# TSOC_USBUART2_pwr.net
KiCad netlist of a schematic drawn in EAGLE
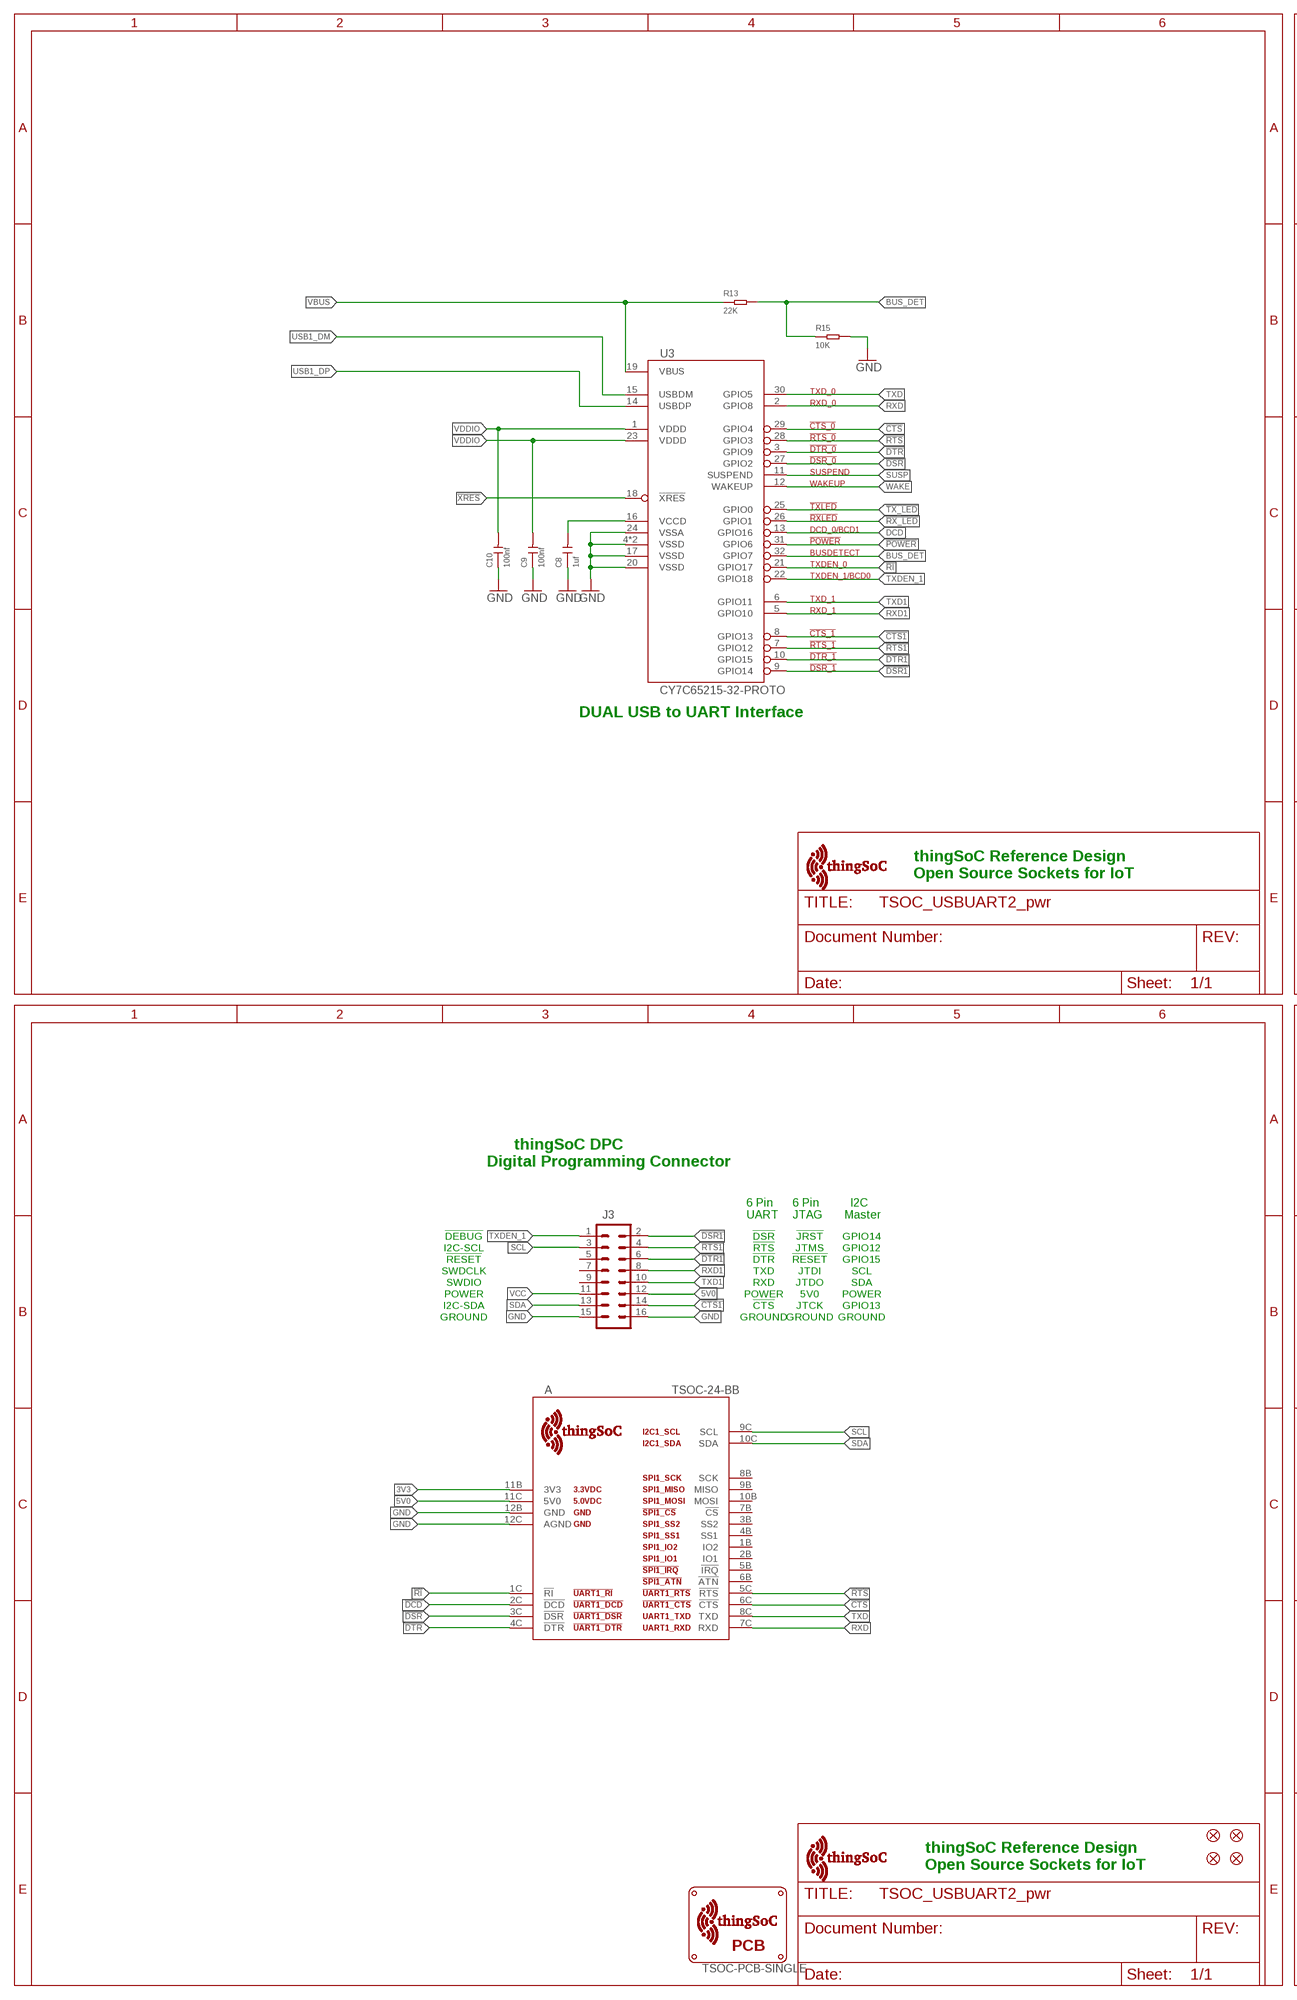
[diagram p0: schematic, sheet 1, part 1 of 2]
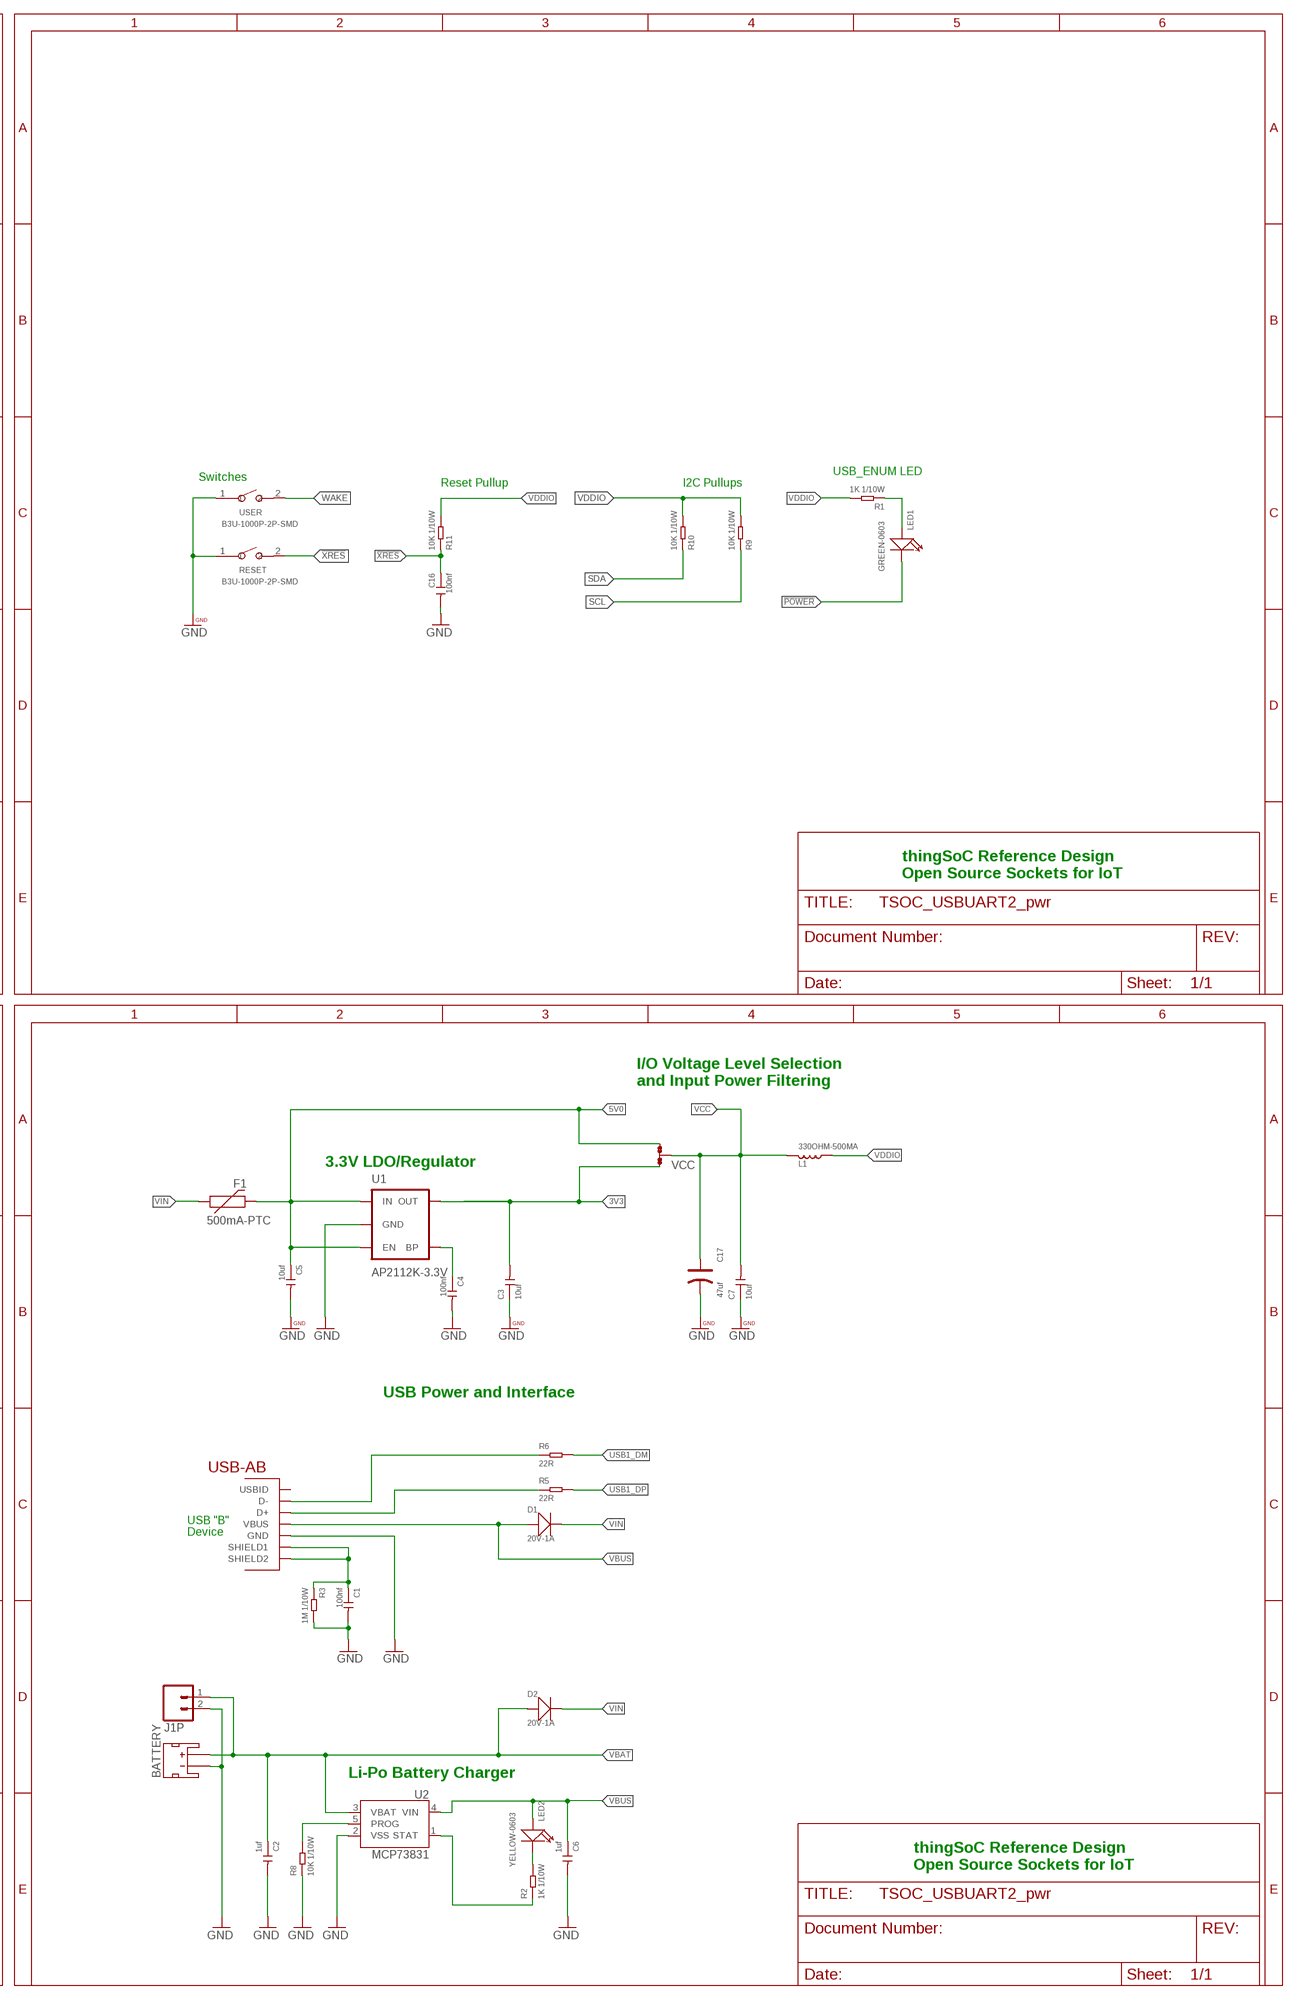
[diagram p1: schematic, sheet 1, part 2 of 2]

(export (version "E")
  (design (tool "Eeschema 10.0.6"))
  (components
    (comp (ref "A")
      (value "TSOC-24-BB")
      (footprint "eagle-import:TSOC-BB-S24")
      (libsource (lib "eagle-import") (part "TSOC-24-BB"))
    )
    (comp (ref "BATTERY")
      (value "JST_2MM_MALE")
      (footprint "eagle-import:JST-2-SMD")
      (libsource (lib "eagle-import") (part "JST_2MM_MALE"))
    )
    (comp (ref "C1")
      (value "100nf")
      (footprint "eagle-import:C0603")
      (fields (field (name "MPN") "CC0603KRX7R9BB104"))
      (libsource (lib "eagle-import") (part "CERAMIC-100NF-50V-10%-X7R(0603)"))
    )
    (comp (ref "C2")
      (value "1uf")
      (footprint "eagle-import:C0603")
      (fields (field (name "MPN") "CC0603KRX7R8BB105"))
      (libsource (lib "eagle-import") (part "CERAMIC-1UF-25V-10%-X7R(0603)"))
    )
    (comp (ref "C3")
      (value "10uf")
      (footprint "eagle-import:C0603")
      (fields (field (name "MPN") "CC0603KRX5R6BB106"))
      (libsource (lib "eagle-import") (part "CERAMIC-10UF-10V-10%-X5R(0603)"))
    )
    (comp (ref "C4")
      (value "100nf")
      (footprint "eagle-import:C0603")
      (fields (field (name "MPN") "CC0603KRX7R9BB104"))
      (libsource (lib "eagle-import") (part "CERAMIC-100NF-50V-10%-X7R(0603)"))
    )
    (comp (ref "C5")
      (value "10uf")
      (footprint "eagle-import:C0603")
      (fields (field (name "MPN") "CC0603KRX5R6BB106"))
      (libsource (lib "eagle-import") (part "CERAMIC-10UF-10V-10%-X5R(0603)"))
    )
    (comp (ref "C6")
      (value "1uf")
      (footprint "eagle-import:C0603")
      (fields (field (name "MPN") "CC0603KRX7R8BB105"))
      (libsource (lib "eagle-import") (part "CERAMIC-1UF-25V-10%-X7R(0603)"))
    )
    (comp (ref "C7")
      (value "10uf")
      (footprint "eagle-import:C0603")
      (fields (field (name "MPN") "CC0603KRX5R6BB106"))
      (libsource (lib "eagle-import") (part "CERAMIC-10UF-10V-10%-X5R(0603)"))
    )
    (comp (ref "C8")
      (value "1uf")
      (footprint "eagle-import:C0603")
      (fields (field (name "MPN") "CC0603KRX7R8BB105"))
      (libsource (lib "eagle-import") (part "CERAMIC-1UF-25V-10%-X7R(0603)"))
    )
    (comp (ref "C9")
      (value "100nf")
      (footprint "eagle-import:C0603")
      (fields (field (name "MPN") "CC0603KRX7R9BB104"))
      (libsource (lib "eagle-import") (part "CERAMIC-100NF-50V-10%-X7R(0603)"))
    )
    (comp (ref "C10")
      (value "100nf")
      (footprint "eagle-import:C0603")
      (fields (field (name "MPN") "CC0603KRX7R9BB104"))
      (libsource (lib "eagle-import") (part "CERAMIC-100NF-50V-10%-X7R(0603)"))
    )
    (comp (ref "C16")
      (value "100nf")
      (footprint "eagle-import:C0603")
      (fields (field (name "MPN") "CC0603KRX7R9BB104"))
      (libsource (lib "eagle-import") (part "CERAMIC-100NF-50V-10%-X7R(0603)"))
    )
    (comp (ref "C17")
      (value "47uf")
      (footprint "eagle-import:AVX-A")
      (fields (field (name "MPN") "TAJA476*006#NJ"))
      (libsource (lib "eagle-import") (part "TANTALUM-SMD-47UF-6.3V(AVX-A)"))
    )
    (comp (ref "D1")
      (value "20V-1A")
      (footprint "eagle-import:SOD-123")
      (fields (field (name "MPN") "B5819W"))
      (libsource (lib "eagle-import") (part "SMD-DIODE-SCHOTTKY-20V-1A(SOD-123)"))
    )
    (comp (ref "D2")
      (value "20V-1A")
      (footprint "eagle-import:SOD-123")
      (fields (field (name "MPN") "B5819W"))
      (libsource (lib "eagle-import") (part "SMD-DIODE-SCHOTTKY-20V-1A(SOD-123)"))
    )
    (comp (ref "F1")
      (value "500mA-PTC")
      (footprint "eagle-import:PTC-1206")
      (libsource (lib "eagle-import") (part "PTCSMD"))
    )
    (comp (ref "FID1")
      (value "FIDUCIALUFIDUCIAL")
      (footprint "eagle-import:MICRO-FIDUCIAL")
      (libsource (lib "eagle-import") (part "FIDUCIALUFIDUCIAL"))
    )
    (comp (ref "FID2")
      (value "FIDUCIALUFIDUCIAL")
      (footprint "eagle-import:MICRO-FIDUCIAL")
      (libsource (lib "eagle-import") (part "FIDUCIALUFIDUCIAL"))
    )
    (comp (ref "FID3")
      (value "FIDUCIALUFIDUCIAL")
      (footprint "eagle-import:MICRO-FIDUCIAL")
      (libsource (lib "eagle-import") (part "FIDUCIALUFIDUCIAL"))
    )
    (comp (ref "FID4")
      (value "FIDUCIALUFIDUCIAL")
      (footprint "eagle-import:MICRO-FIDUCIAL")
      (libsource (lib "eagle-import") (part "FIDUCIALUFIDUCIAL"))
    )
    (comp (ref "J1P")
      (value "M02-JST-2-PTH-NO_SILK")
      (footprint "eagle-import:JST-2-PTH-NS")
      (libsource (lib "eagle-import") (part "M02-JST-2-PTH-NO_SILK"))
    )
    (comp (ref "J3")
      (value "M08X2")
      (footprint "eagle-import:2X8")
      (libsource (lib "eagle-import") (part "M08X2"))
    )
    (comp (ref "L1")
      (value "330OHM-500MA")
      (footprint "eagle-import:L0603")
      (fields (field (name "MPN") "BLM18AG121SN1D"))
      (libsource (lib "eagle-import") (part "SMD-FERRITE-CHIP-120-OHM-500MA(0603)"))
    )
    (comp (ref "LED1")
      (value "GREEN-0603")
      (footprint "eagle-import:LED-0603")
      (fields (field (name "MPN") "19-217-G7C-AN1P2-3T"))
      (libsource (lib "eagle-import") (part "SMD-LED-CLEAR-GREEN(0603)"))
    )
    (comp (ref "LED2")
      (value "YELLOW-0603")
      (footprint "eagle-import:LED-0603")
      (fields (field (name "MPN") "19-217-Y5C-AM1N1VY-3T"))
      (libsource (lib "eagle-import") (part "SMD-LED-CLEAR-YELLOW(0603)"))
    )
    (comp (ref "R1")
      (value "1K 1/10W")
      (footprint "eagle-import:R0603")
      (fields (field (name "MPN") "RC0603JR-071KL"))
      (libsource (lib "eagle-import") (part "SMD-RES-1K-5%-1/10W(0603)"))
    )
    (comp (ref "R2")
      (value "1K 1/10W")
      (footprint "eagle-import:R0603")
      (fields (field (name "MPN") "RC0603JR-071KL"))
      (libsource (lib "eagle-import") (part "SMD-RES-1K-5%-1/10W(0603)"))
    )
    (comp (ref "R3")
      (value "1M 1/10W")
      (footprint "eagle-import:R0603")
      (fields (field (name "MPN") "RC0603JR-071ML"))
      (libsource (lib "eagle-import") (part "SMD-RES-1M-5%-1/10W(0603)"))
    )
    (comp (ref "R5")
      (value "22R")
      (footprint "eagle-import:R0603")
      (fields (field (name "MPN") "RC0603JR-0722RL"))
      (libsource (lib "eagle-import") (part "SMD-RES-22R-5%-1/10W(0603)"))
    )
    (comp (ref "R6")
      (value "22R")
      (footprint "eagle-import:R0603")
      (fields (field (name "MPN") "RC0603JR-0722RL"))
      (libsource (lib "eagle-import") (part "SMD-RES-22R-5%-1/10W(0603)"))
    )
    (comp (ref "R8")
      (value "10K 1/10W")
      (footprint "eagle-import:R0603")
      (fields (field (name "MPN") "RC0603JR-0710KL"))
      (libsource (lib "eagle-import") (part "SMD-RES-10K-5%-1/10W(0603)"))
    )
    (comp (ref "R9")
      (value "10K 1/10W")
      (footprint "eagle-import:R0603")
      (fields (field (name "MPN") "RC0603JR-0710KL"))
      (libsource (lib "eagle-import") (part "SMD-RES-10K-5%-1/10W(0603)"))
    )
    (comp (ref "R10")
      (value "10K 1/10W")
      (footprint "eagle-import:R0603")
      (fields (field (name "MPN") "RC0603JR-0710KL"))
      (libsource (lib "eagle-import") (part "SMD-RES-10K-5%-1/10W(0603)"))
    )
    (comp (ref "R11")
      (value "10K 1/10W")
      (footprint "eagle-import:R0603")
      (fields (field (name "MPN") "RC0603JR-0710KL"))
      (libsource (lib "eagle-import") (part "SMD-RES-10K-5%-1/10W(0603)"))
    )
    (comp (ref "R13")
      (value "22K")
      (footprint "eagle-import:R0603")
      (fields (field (name "MPN") "RC0603JR-0722KL"))
      (libsource (lib "eagle-import") (part "SMD-RES-22K-5%-1/10W(0603)"))
    )
    (comp (ref "R15")
      (value "10K")
      (footprint "eagle-import:R0603")
      (fields (field (name "MPN") "RC0603FR-0710KL"))
      (libsource (lib "eagle-import") (part "SMD-RES-10K-1%-1/10W(0603)"))
    )
    (comp (ref "RESET")
      (value "B3U-1000P-2P-SMD")
      (footprint "eagle-import:SW2-2.6-3.0X2.5X1.2+0.4MM")
      (libsource (lib "eagle-import") (part "SMD-BUTTON(2P-3.0X2.5X1.2+0.4MM)-B3U-1000P-2P-SMD"))
    )
    (comp (ref "U$1")
      (value "TSOC-PCB-SINGLE")
      (footprint "eagle-import:TSOC-BB-BRD-DIM")
      (libsource (lib "eagle-import") (part "TSOC-PCB-SINGLE"))
    )
    (comp (ref "U$100")
      (value "TSOC-LOGO-LRG")
      (footprint "eagle-import:TSOC-LOGO-LRG")
      (libsource (lib "eagle-import") (part "TSOC-LOGO-LRG"))
    )
    (comp (ref "U$101")
      (value "TSOC-LOGO-SMALL")
      (footprint "eagle-import:TSOC-LOGO-SML")
      (libsource (lib "eagle-import") (part "TSOC-LOGO-SMALL"))
    )
    (comp (ref "U1")
      (value "AP2112K-3.3V")
      (footprint "eagle-import:SOT23-5")
      (libsource (lib "eagle-import") (part "V_REG_LDOSMD"))
    )
    (comp (ref "U2")
      (value "MCP73831")
      (footprint "eagle-import:SOT23-5")
      (libsource (lib "eagle-import") (part "MCP73831"))
    )
    (comp (ref "U3")
      (value "CY7C65215-32-PROTO")
      (footprint "eagle-import:QFN32-PROTO")
      (libsource (lib "eagle-import") (part "CY7C65215-32-PROTO"))
    )
    (comp (ref "USB")
      (value "USB_AB")
      (footprint "eagle-import:USB-AB-MICRO-SMD")
      (libsource (lib "eagle-import") (part "USB_AB"))
    )
    (comp (ref "USER")
      (value "B3U-1000P-2P-SMD")
      (footprint "eagle-import:SW2-2.6-3.0X2.5X1.2+0.4MM")
      (libsource (lib "eagle-import") (part "SMD-BUTTON(2P-3.0X2.5X1.2+0.4MM)-B3U-1000P-2P-SMD"))
    )
    (comp (ref "VCC")
      (value "JMP-3-1_2")
      (footprint "eagle-import:JMP-3-1_2")
      (libsource (lib "eagle-import") (part "JMP-3-1_2"))
    )
  )
  (nets
    (net (code "1") (name "/~{CTS1}") (class "Default")
      (node (ref "J3") (pin "14") (pinfunction "14_14") (pintype "passive"))
      (node (ref "U3") (pin "8") (pinfunction "GPIO13_8") (pintype "input"))
    )
    (net (code "2") (name "/~{CTS}") (class "Default")
      (node (ref "A") (pin "6C") (pinfunction "~{CTS}_6C") (pintype "bidirectional"))
      (node (ref "U3") (pin "29") (pinfunction "GPIO4_29") (pintype "input"))
    )
    (net (code "3") (name "/~{DCD}") (class "Default")
      (node (ref "A") (pin "2C") (pinfunction "~{DCD}_2C") (pintype "bidirectional"))
    )
    (net (code "4") (name "/~{DSR1}") (class "Default")
      (node (ref "J3") (pin "2") (pinfunction "2_2") (pintype "passive"))
      (node (ref "U3") (pin "9") (pinfunction "GPIO14_9") (pintype "input"))
    )
    (net (code "5") (name "/~{DSR}") (class "Default")
      (node (ref "A") (pin "3C") (pinfunction "~{DSR}_3C") (pintype "bidirectional"))
      (node (ref "U3") (pin "27") (pinfunction "GPIO2_27") (pintype "input"))
    )
    (net (code "6") (name "/~{DTR1}") (class "Default")
      (node (ref "J3") (pin "6") (pinfunction "6_6") (pintype "passive"))
      (node (ref "U3") (pin "10") (pinfunction "GPIO15_10") (pintype "output"))
    )
    (net (code "7") (name "/~{DTR}") (class "Default")
      (node (ref "A") (pin "4C") (pinfunction "~{DTR}_4C") (pintype "bidirectional"))
      (node (ref "U3") (pin "3") (pinfunction "GPIO9_3") (pintype "output"))
    )
    (net (code "8") (name "/~{POWER}") (class "Default")
      (node (ref "LED1") (pin "-") (pinfunction "-_-") (pintype "passive"))
      (node (ref "U3") (pin "31") (pinfunction "GPIO6_31") (pintype "input"))
    )
    (net (code "9") (name "/~{RI}") (class "Default")
      (node (ref "A") (pin "1C") (pinfunction "~{RI}_1C") (pintype "bidirectional"))
      (node (ref "U3") (pin "21") (pinfunction "GPIO17_21") (pintype "input"))
    )
    (net (code "10") (name "/~{RTS1}") (class "Default")
      (node (ref "J3") (pin "4") (pinfunction "4_4") (pintype "passive"))
      (node (ref "U3") (pin "7") (pinfunction "GPIO12_7") (pintype "output"))
    )
    (net (code "11") (name "/~{RTS}") (class "Default")
      (node (ref "A") (pin "5C") (pinfunction "~{RTS}_5C") (pintype "bidirectional"))
      (node (ref "U3") (pin "28") (pinfunction "GPIO3_28") (pintype "output"))
    )
    (net (code "12") (name "/~{RX_LED}") (class "Default")
      (node (ref "U3") (pin "26") (pinfunction "GPIO1_26") (pintype "input"))
    )
    (net (code "13") (name "/~{TX_LED}") (class "Default")
      (node (ref "U3") (pin "25") (pinfunction "GPIO0_25") (pintype "input"))
    )
    (net (code "14") (name "/~{XRES}") (class "Default")
      (node (ref "C16") (pin "1") (pinfunction "1_1") (pintype "passive"))
      (node (ref "R11") (pin "1") (pinfunction "1_1") (pintype "passive"))
      (node (ref "RESET") (pin "2") (pinfunction "2_2") (pintype "bidirectional"))
      (node (ref "U3") (pin "18") (pinfunction "~{XRES}_18") (pintype "input"))
    )
    (net (code "15") (name "3V3") (class "Default")
      (node (ref "A") (pin "11B") (pinfunction "3V3_11B") (pintype "bidirectional"))
      (node (ref "C3") (pin "2") (pinfunction "2_2") (pintype "passive"))
      (node (ref "U1") (pin "5") (pinfunction "OUT_5") (pintype "passive"))
      (node (ref "VCC") (pin "1") (pinfunction "1_1") (pintype "passive"))
    )
    (net (code "16") (name "5V0") (class "Default")
      (node (ref "A") (pin "11C") (pinfunction "5V0_11C") (pintype "bidirectional"))
      (node (ref "C5") (pin "1") (pinfunction "1_1") (pintype "passive"))
      (node (ref "F1") (pin "2") (pinfunction "2_2") (pintype "bidirectional"))
      (node (ref "J3") (pin "12") (pinfunction "12_12") (pintype "passive"))
      (node (ref "U1") (pin "1") (pinfunction "IN_1") (pintype "input"))
      (node (ref "U1") (pin "3") (pinfunction "EN_3") (pintype "input"))
      (node (ref "VCC") (pin "3") (pinfunction "3_3") (pintype "passive"))
    )
    (net (code "17") (name "BUS_DET") (class "Default")
      (node (ref "R13") (pin "2") (pinfunction "2_2") (pintype "passive"))
      (node (ref "R15") (pin "1") (pinfunction "1_1") (pintype "passive"))
      (node (ref "U3") (pin "32") (pinfunction "GPIO7_32") (pintype "input"))
    )
    (net (code "18") (name "DCD") (class "Default")
      (node (ref "U3") (pin "13") (pinfunction "GPIO16_13") (pintype "output"))
    )
    (net (code "19") (name "GND") (class "Default")
      (node (ref "A") (pin "12B") (pinfunction "GND_12B") (pintype "bidirectional"))
      (node (ref "A") (pin "12C") (pinfunction "AGND_12C") (pintype "bidirectional"))
      (node (ref "BATTERY") (pin "1") (pinfunction "-_1") (pintype "bidirectional"))
      (node (ref "C1") (pin "2") (pinfunction "2_2") (pintype "passive"))
      (node (ref "C10") (pin "1") (pinfunction "1_1") (pintype "passive"))
      (node (ref "C16") (pin "2") (pinfunction "2_2") (pintype "passive"))
      (node (ref "C17") (pin "-") (pinfunction "-_-") (pintype "passive"))
      (node (ref "C2") (pin "2") (pinfunction "2_2") (pintype "passive"))
      (node (ref "C3") (pin "1") (pinfunction "1_1") (pintype "passive"))
      (node (ref "C4") (pin "2") (pinfunction "2_2") (pintype "passive"))
      (node (ref "C5") (pin "2") (pinfunction "2_2") (pintype "passive"))
      (node (ref "C6") (pin "2") (pinfunction "2_2") (pintype "passive"))
      (node (ref "C7") (pin "1") (pinfunction "1_1") (pintype "passive"))
      (node (ref "C8") (pin "1") (pinfunction "1_1") (pintype "passive"))
      (node (ref "C9") (pin "1") (pinfunction "1_1") (pintype "passive"))
      (node (ref "J1P") (pin "2") (pinfunction "2_2") (pintype "passive"))
      (node (ref "J3") (pin "15") (pinfunction "15_15") (pintype "passive"))
      (node (ref "J3") (pin "16") (pinfunction "16_16") (pintype "passive"))
      (node (ref "R15") (pin "2") (pinfunction "2_2") (pintype "passive"))
      (node (ref "R3") (pin "2") (pinfunction "2_2") (pintype "passive"))
      (node (ref "R8") (pin "1") (pinfunction "1_1") (pintype "passive"))
      (node (ref "RESET") (pin "1") (pinfunction "1_1") (pintype "bidirectional"))
      (node (ref "U1") (pin "2") (pinfunction "GND_2") (pintype "input"))
      (node (ref "U2") (pin "2") (pinfunction "VSS_2") (pintype "power_in"))
      (node (ref "U3") (pin "17") (pinfunction "VSSD_17") (pintype "power_in"))
      (node (ref "U3") (pin "20") (pinfunction "VSSD_20") (pintype "power_in"))
      (node (ref "U3") (pin "24") (pinfunction "VSSA_24") (pintype "power_in"))
      (node (ref "U3") (pin "4") (pinfunction "VSSD_4") (pintype "power_in"))
      (node (ref "U3") (pin "EXP") (pinfunction "VSSD_EXP") (pintype "power_in"))
      (node (ref "USB") (pin "GND") (pinfunction "GND_GND") (pintype "bidirectional"))
      (node (ref "USER") (pin "1") (pinfunction "1_1") (pintype "bidirectional"))
    )
    (net (code "20") (name "Net-(C1-Pad1)") (class "Default")
      (node (ref "C1") (pin "1") (pinfunction "1_1") (pintype "passive"))
      (node (ref "R3") (pin "1") (pinfunction "1_1") (pintype "passive"))
      (node (ref "USB") (pin "SHIELD1") (pinfunction "SHIELD1_SHIELD1") (pintype "bidirectional"))
      (node (ref "USB") (pin "SHIELD2") (pinfunction "SHIELD2_SHIELD2") (pintype "bidirectional"))
    )
    (net (code "21") (name "Net-(LED1-Pad+)") (class "Default")
      (node (ref "LED1") (pin "+") (pinfunction "+_+") (pintype "passive"))
      (node (ref "R1") (pin "1") (pinfunction "1_1") (pintype "passive"))
    )
    (net (code "22") (name "Net-(LED2-Pad-)") (class "Default")
      (node (ref "LED2") (pin "-") (pinfunction "-_-") (pintype "passive"))
      (node (ref "R2") (pin "2") (pinfunction "2_2") (pintype "passive"))
    )
    (net (code "23") (name "Net-(R5-Pad1)") (class "Default")
      (node (ref "R5") (pin "1") (pinfunction "1_1") (pintype "passive"))
      (node (ref "USB") (pin "D+") (pinfunction "D+_D+") (pintype "bidirectional"))
    )
    (net (code "24") (name "Net-(R6-Pad1)") (class "Default")
      (node (ref "R6") (pin "1") (pinfunction "1_1") (pintype "passive"))
      (node (ref "USB") (pin "D-") (pinfunction "D-_D-") (pintype "bidirectional"))
    )
    (net (code "25") (name "Net-(U1-BP)") (class "Default")
      (node (ref "C4") (pin "1") (pinfunction "1_1") (pintype "passive"))
      (node (ref "U1") (pin "4") (pinfunction "BP_4") (pintype "input"))
    )
    (net (code "26") (name "Net-(U2-PROG)") (class "Default")
      (node (ref "R8") (pin "2") (pinfunction "2_2") (pintype "passive"))
      (node (ref "U2") (pin "5") (pinfunction "PROG_5") (pintype "input"))
    )
    (net (code "27") (name "Net-(U2-STAT)") (class "Default")
      (node (ref "R2") (pin "1") (pinfunction "1_1") (pintype "passive"))
      (node (ref "U2") (pin "1") (pinfunction "STAT_1") (pintype "output"))
    )
    (net (code "28") (name "Net-(U3-VCCD)") (class "Default")
      (node (ref "C8") (pin "2") (pinfunction "2_2") (pintype "passive"))
      (node (ref "U3") (pin "16") (pinfunction "VCCD_16") (pintype "output"))
    )
    (net (code "29") (name "RXD") (class "Default")
      (node (ref "A") (pin "7C") (pinfunction "RXD_7C") (pintype "bidirectional"))
      (node (ref "U3") (pin "2") (pinfunction "GPIO8_2") (pintype "input"))
    )
    (net (code "30") (name "RXD1") (class "Default")
      (node (ref "J3") (pin "8") (pinfunction "8_8") (pintype "passive"))
      (node (ref "U3") (pin "5") (pinfunction "GPIO10_5") (pintype "input"))
    )
    (net (code "31") (name "SCL") (class "Default")
      (node (ref "A") (pin "9C") (pinfunction "SCL_9C") (pintype "bidirectional"))
      (node (ref "J3") (pin "3") (pinfunction "3_3") (pintype "passive"))
      (node (ref "R9") (pin "1") (pinfunction "1_1") (pintype "passive"))
    )
    (net (code "32") (name "SDA") (class "Default")
      (node (ref "A") (pin "10C") (pinfunction "SDA_10C") (pintype "bidirectional"))
      (node (ref "J3") (pin "13") (pinfunction "13_13") (pintype "passive"))
      (node (ref "R10") (pin "1") (pinfunction "1_1") (pintype "passive"))
    )
    (net (code "33") (name "SUSP") (class "Default")
      (node (ref "U3") (pin "11") (pinfunction "SUSPEND_11") (pintype "input"))
    )
    (net (code "34") (name "TXD") (class "Default")
      (node (ref "A") (pin "8C") (pinfunction "TXD_8C") (pintype "bidirectional"))
      (node (ref "U3") (pin "30") (pinfunction "GPIO5_30") (pintype "output"))
    )
    (net (code "35") (name "TXD1") (class "Default")
      (node (ref "J3") (pin "10") (pinfunction "10_10") (pintype "passive"))
      (node (ref "U3") (pin "6") (pinfunction "GPIO11_6") (pintype "output"))
    )
    (net (code "36") (name "TXDEN_1") (class "Default")
      (node (ref "J3") (pin "1") (pinfunction "1_1") (pintype "passive"))
      (node (ref "U3") (pin "22") (pinfunction "GPIO18_22") (pintype "input"))
    )
    (net (code "37") (name "USB1_DM") (class "Default")
      (node (ref "R6") (pin "2") (pinfunction "2_2") (pintype "passive"))
      (node (ref "U3") (pin "15") (pinfunction "USBDM_15") (pintype "bidirectional"))
    )
    (net (code "38") (name "USB1_DP") (class "Default")
      (node (ref "R5") (pin "2") (pinfunction "2_2") (pintype "passive"))
      (node (ref "U3") (pin "14") (pinfunction "USBDP_14") (pintype "bidirectional"))
    )
    (net (code "39") (name "VBAT") (class "Default")
      (node (ref "BATTERY") (pin "2") (pinfunction "+_2") (pintype "bidirectional"))
      (node (ref "C2") (pin "1") (pinfunction "1_1") (pintype "passive"))
      (node (ref "D2") (pin "+") (pinfunction "+_+") (pintype "passive"))
      (node (ref "J1P") (pin "1") (pinfunction "1_1") (pintype "passive"))
      (node (ref "U2") (pin "3") (pinfunction "VBAT_3") (pintype "power_in"))
    )
    (net (code "40") (name "VBUS") (class "Default")
      (node (ref "C6") (pin "1") (pinfunction "1_1") (pintype "passive"))
      (node (ref "D1") (pin "+") (pinfunction "+_+") (pintype "passive"))
      (node (ref "LED2") (pin "+") (pinfunction "+_+") (pintype "passive"))
      (node (ref "R13") (pin "1") (pinfunction "1_1") (pintype "passive"))
      (node (ref "U2") (pin "4") (pinfunction "VIN_4") (pintype "power_in"))
      (node (ref "U3") (pin "19") (pinfunction "VBUS_19") (pintype "power_in"))
      (node (ref "USB") (pin "VBUS") (pinfunction "VBUS_VBUS") (pintype "bidirectional"))
    )
    (net (code "41") (name "VCC") (class "Default")
      (node (ref "C17") (pin "+") (pinfunction "+_+") (pintype "passive"))
      (node (ref "C7") (pin "2") (pinfunction "2_2") (pintype "passive"))
      (node (ref "J3") (pin "11") (pinfunction "11_11") (pintype "passive"))
      (node (ref "L1") (pin "1") (pinfunction "1_1") (pintype "passive"))
      (node (ref "VCC") (pin "2") (pinfunction "2_2") (pintype "passive"))
    )
    (net (code "42") (name "VDDIO") (class "Default")
      (node (ref "C10") (pin "2") (pinfunction "2_2") (pintype "passive"))
      (node (ref "C9") (pin "2") (pinfunction "2_2") (pintype "passive"))
      (node (ref "L1") (pin "2") (pinfunction "2_2") (pintype "passive"))
      (node (ref "R1") (pin "2") (pinfunction "2_2") (pintype "passive"))
      (node (ref "R10") (pin "2") (pinfunction "2_2") (pintype "passive"))
      (node (ref "R11") (pin "2") (pinfunction "2_2") (pintype "passive"))
      (node (ref "R9") (pin "2") (pinfunction "2_2") (pintype "passive"))
      (node (ref "U3") (pin "1") (pinfunction "VDDD_1") (pintype "power_in"))
      (node (ref "U3") (pin "23") (pinfunction "VDDD_23") (pintype "power_in"))
    )
    (net (code "43") (name "VIN") (class "Default")
      (node (ref "D1") (pin "-") (pinfunction "-_-") (pintype "passive"))
      (node (ref "D2") (pin "-") (pinfunction "-_-") (pintype "passive"))
      (node (ref "F1") (pin "1") (pinfunction "1_1") (pintype "bidirectional"))
    )
    (net (code "44") (name "WAKE") (class "Default")
      (node (ref "U3") (pin "12") (pinfunction "WAKEUP_12") (pintype "input"))
      (node (ref "USER") (pin "2") (pinfunction "2_2") (pintype "bidirectional"))
    )
    (net (code "45") (name "unconnected-(A-IO1-Pad2B)") (class "Default")
      (node (ref "A") (pin "2B") (pinfunction "IO1_2B") (pintype "bidirectional"))
    )
    (net (code "46") (name "unconnected-(A-IO2-Pad1B)") (class "Default")
      (node (ref "A") (pin "1B") (pinfunction "IO2_1B") (pintype "bidirectional"))
    )
    (net (code "47") (name "unconnected-(A-MISO-Pad9B)") (class "Default")
      (node (ref "A") (pin "9B") (pinfunction "MISO_9B") (pintype "bidirectional"))
    )
    (net (code "48") (name "unconnected-(A-MOSI-Pad10B)") (class "Default")
      (node (ref "A") (pin "10B") (pinfunction "MOSI_10B") (pintype "bidirectional"))
    )
    (net (code "49") (name "unconnected-(A-SCK-Pad8B)") (class "Default")
      (node (ref "A") (pin "8B") (pinfunction "SCK_8B") (pintype "bidirectional"))
    )
    (net (code "50") (name "unconnected-(A-SS1-Pad4B)") (class "Default")
      (node (ref "A") (pin "4B") (pinfunction "SS1_4B") (pintype "bidirectional"))
    )
    (net (code "51") (name "unconnected-(A-SS2-Pad3B)") (class "Default")
      (node (ref "A") (pin "3B") (pinfunction "SS2_3B") (pintype "bidirectional"))
    )
    (net (code "52") (name "unconnected-(A-~{ATN}-Pad6B)") (class "Default")
      (node (ref "A") (pin "6B") (pinfunction "~{ATN}_6B") (pintype "bidirectional"))
    )
    (net (code "53") (name "unconnected-(A-~{CS}-Pad7B)") (class "Default")
      (node (ref "A") (pin "7B") (pinfunction "~{CS}_7B") (pintype "bidirectional"))
    )
    (net (code "54") (name "unconnected-(A-~{IRQ}-Pad5B)") (class "Default")
      (node (ref "A") (pin "5B") (pinfunction "~{IRQ}_5B") (pintype "bidirectional"))
    )
    (net (code "55") (name "unconnected-(BATTERY-PAD1-PadNC1)") (class "Default")
      (node (ref "BATTERY") (pin "NC1") (pinfunction "PAD1_NC1") (pintype "bidirectional"))
    )
    (net (code "56") (name "unconnected-(BATTERY-PAD2-PadNC2)") (class "Default")
      (node (ref "BATTERY") (pin "NC2") (pinfunction "PAD2_NC2") (pintype "bidirectional"))
    )
    (net (code "57") (name "unconnected-(J3-Pad5)") (class "Default")
      (node (ref "J3") (pin "5") (pinfunction "5_5") (pintype "passive"))
    )
    (net (code "58") (name "unconnected-(J3-Pad7)") (class "Default")
      (node (ref "J3") (pin "7") (pinfunction "7_7") (pintype "passive"))
    )
    (net (code "59") (name "unconnected-(J3-Pad9)") (class "Default")
      (node (ref "J3") (pin "9") (pinfunction "9_9") (pintype "passive"))
    )
    (net (code "60") (name "unconnected-(USB-USBID-PadID)") (class "Default")
      (node (ref "USB") (pin "ID") (pinfunction "USBID_ID") (pintype "bidirectional"))
    )
  )
)
